# Sheet1.net
KiCad netlist of a schematic drawn in Altium Designer
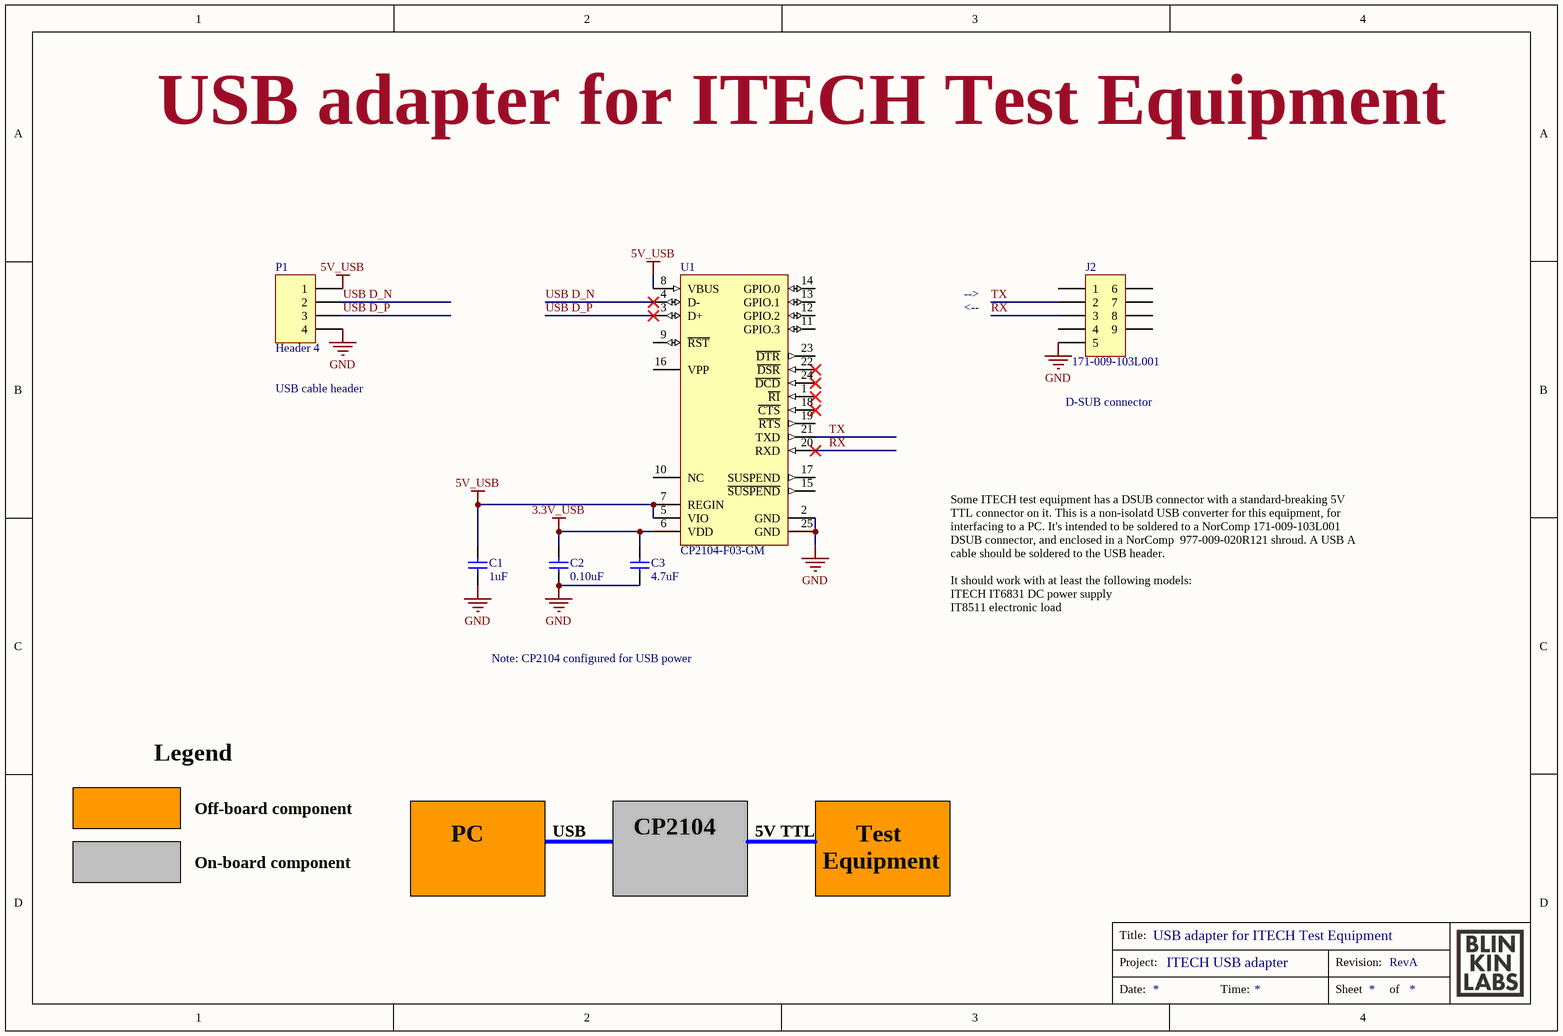
[diagram p0: Sheet1.SchDoc]

(export (version "E")
  (design (tool "Eeschema 10.0.6"))
  (components
    (comp (ref "C1")
      (value "1uF")
      (footprint "CAPC1005X06L")
      (description "CAP CER 1UF 10V X5R 0402")
      (fields
        (field (name "PARTNUMBER") "GRM155R61A105KE15D")
        (field (name "DIGI-KEY PART NUMBER") "490-3890-1-ND")
      )
      (libsource (lib "cap_murata") (part "CAPACITOR"))
    )
    (comp (ref "C2")
      (value "0.10uF")
      (footprint "CAPC1005X06L")
      (description "CAP CER 0.1UF 10V X5R 0402")
      (fields
        (field (name "DIGI-KEY PART NUMBER") "490-10009-1-ND")
        (field (name "MANUFACTURER") "Murata Electronics North America")
      )
      (libsource (lib "cap_murata") (part "CAPACITOR"))
    )
    (comp (ref "C3")
      (value "4.7uF")
      (footprint "CAPC1005X06L")
      (description "CAP CER 4.7UF 6.3V X5R 0402")
      (fields
        (field (name "PARTNUMBER") "GRM155R60J475ME47D")
        (field (name "DIGI-KEY PART NUMBER") "490-5915-1-ND")
      )
      (libsource (lib "cap_murata") (part "CAPACITOR"))
    )
    (comp (ref "J2")
      (value "171-009-103L001")
      (footprint "171-009-103L001")
      (description "CONN D-SUB PLUG 9POS PNL MNT, side mount DSUB connector")
      (fields (field (name "MANUFACTURER") "NorComp Inc.") (field (name "DIGIKEY PARTNUMBER") "209ME-ND"))
      (libsource (lib "Blinkinlabs") (part "171-009-103L001"))
    )
    (comp (ref "P1")
      (value "Header 4")
      (footprint "HDR1X4")
      (description "Header, 4-Pin")
      (fields (field (name "PUBLISHER") "Altium Limited"))
      (libsource (lib "Miscellaneous Connectors") (part "Header 4"))
    )
    (comp (ref "U1")
      (value "CP2104-F03-GM")
      (footprint "SLAB-QFN-24-2675x2675TP_M")
      (fields (field (name "MANUFACTURER") "Silicon Labs"))
      (libsource (lib "Altium Content Vault") (part "SLAB-CP2104-QFN-24-25"))
    )
  )
  (nets
    (net (code "1") (name "/RX") (class "Default")
      (node (ref "J2") (pin "3") (pinfunction "3_3") (pintype "passive"))
      (node (ref "U1") (pin "20") (pinfunction "RXD_20") (pintype "input"))
    )
    (net (code "2") (name "/TX") (class "Default")
      (node (ref "J2") (pin "2") (pinfunction "2_2") (pintype "passive"))
      (node (ref "U1") (pin "21") (pinfunction "TXD_21") (pintype "output"))
    )
    (net (code "3") (name "/USB D_N") (class "Default")
      (node (ref "P1") (pin "2") (pinfunction "2_2") (pintype "passive"))
      (node (ref "U1") (pin "4") (pinfunction "D-_4") (pintype "bidirectional"))
    )
    (net (code "4") (name "/USB D_P") (class "Default")
      (node (ref "P1") (pin "3") (pinfunction "3_3") (pintype "passive"))
      (node (ref "U1") (pin "3") (pinfunction "D+_3") (pintype "bidirectional"))
    )
    (net (code "5") (name "3.3V_USB") (class "Default")
      (node (ref "C2") (pin "2") (pinfunction "2_2") (pintype "passive"))
      (node (ref "C3") (pin "1") (pinfunction "1_1") (pintype "passive"))
      (node (ref "U1") (pin "6") (pinfunction "VDD_6") (pintype "power_in"))
    )
    (net (code "6") (name "5V_USB") (class "Default")
      (node (ref "C1") (pin "1") (pinfunction "1_1") (pintype "passive"))
      (node (ref "P1") (pin "1") (pinfunction "1_1") (pintype "passive"))
      (node (ref "U1") (pin "5") (pinfunction "VIO_5") (pintype "power_in"))
      (node (ref "U1") (pin "7") (pinfunction "REGIN_7") (pintype "power_in"))
      (node (ref "U1") (pin "8") (pinfunction "VBUS_8") (pintype "input"))
    )
    (net (code "7") (name "GND") (class "Default")
      (node (ref "C1") (pin "2") (pinfunction "2_2") (pintype "passive"))
      (node (ref "C2") (pin "1") (pinfunction "1_1") (pintype "passive"))
      (node (ref "C3") (pin "2") (pinfunction "2_2") (pintype "passive"))
      (node (ref "J2") (pin "5") (pinfunction "5_5") (pintype "passive"))
      (node (ref "P1") (pin "4") (pinfunction "4_4") (pintype "passive"))
      (node (ref "U1") (pin "2") (pinfunction "GND_2") (pintype "power_in"))
      (node (ref "U1") (pin "25") (pinfunction "GND_25") (pintype "power_in"))
    )
    (net (code "8") (name "unconnected-(J2-Pad1)") (class "Default")
      (node (ref "J2") (pin "1") (pinfunction "1_1") (pintype "passive"))
    )
    (net (code "9") (name "unconnected-(J2-Pad4)") (class "Default")
      (node (ref "J2") (pin "4") (pinfunction "4_4") (pintype "passive"))
    )
    (net (code "10") (name "unconnected-(J2-Pad6)") (class "Default")
      (node (ref "J2") (pin "6") (pinfunction "6_6") (pintype "passive"))
    )
    (net (code "11") (name "unconnected-(J2-Pad7)") (class "Default")
      (node (ref "J2") (pin "7") (pinfunction "7_7") (pintype "passive"))
    )
    (net (code "12") (name "unconnected-(J2-Pad8)") (class "Default")
      (node (ref "J2") (pin "8") (pinfunction "8_8") (pintype "passive"))
    )
    (net (code "13") (name "unconnected-(J2-Pad9)") (class "Default")
      (node (ref "J2") (pin "9") (pinfunction "9_9") (pintype "passive"))
    )
    (net (code "14") (name "unconnected-(U1-GPIO.0-Pad14)") (class "Default")
      (node (ref "U1") (pin "14") (pinfunction "GPIO.0_14") (pintype "bidirectional"))
    )
    (net (code "15") (name "unconnected-(U1-GPIO.1-Pad13)") (class "Default")
      (node (ref "U1") (pin "13") (pinfunction "GPIO.1_13") (pintype "bidirectional"))
    )
    (net (code "16") (name "unconnected-(U1-GPIO.2-Pad12)") (class "Default")
      (node (ref "U1") (pin "12") (pinfunction "GPIO.2_12") (pintype "bidirectional"))
    )
    (net (code "17") (name "unconnected-(U1-GPIO.3-Pad11)") (class "Default")
      (node (ref "U1") (pin "11") (pinfunction "GPIO.3_11") (pintype "bidirectional"))
    )
    (net (code "18") (name "unconnected-(U1-NC-Pad10)") (class "Default")
      (node (ref "U1") (pin "10") (pinfunction "NC_10") (pintype "passive"))
    )
    (net (code "19") (name "unconnected-(U1-SUSPEND-Pad17)") (class "Default")
      (node (ref "U1") (pin "17") (pinfunction "SUSPEND_17") (pintype "output"))
    )
    (net (code "20") (name "unconnected-(U1-VPP-Pad16)") (class "Default")
      (node (ref "U1") (pin "16") (pinfunction "VPP_16") (pintype "passive"))
    )
    (net (code "21") (name "unconnected-(U1-~{CTS}-Pad18)") (class "Default")
      (node (ref "U1") (pin "18") (pinfunction "~{CTS}_18") (pintype "input+no_connect"))
    )
    (net (code "22") (name "unconnected-(U1-~{DCD}-Pad24)") (class "Default")
      (node (ref "U1") (pin "24") (pinfunction "~{DCD}_24") (pintype "input+no_connect"))
    )
    (net (code "23") (name "unconnected-(U1-~{DSR}-Pad22)") (class "Default")
      (node (ref "U1") (pin "22") (pinfunction "~{DSR}_22") (pintype "input+no_connect"))
    )
    (net (code "24") (name "unconnected-(U1-~{DTR}-Pad23)") (class "Default")
      (node (ref "U1") (pin "23") (pinfunction "~{DTR}_23") (pintype "output"))
    )
    (net (code "25") (name "unconnected-(U1-~{RI}-Pad1)") (class "Default")
      (node (ref "U1") (pin "1") (pinfunction "~{RI}_1") (pintype "input+no_connect"))
    )
    (net (code "26") (name "unconnected-(U1-~{RST}-Pad9)") (class "Default")
      (node (ref "U1") (pin "9") (pinfunction "~{RST}_9") (pintype "bidirectional"))
    )
    (net (code "27") (name "unconnected-(U1-~{RTS}-Pad19)") (class "Default")
      (node (ref "U1") (pin "19") (pinfunction "~{RTS}_19") (pintype "output"))
    )
    (net (code "28") (name "unconnected-(U1-~{SUSPEND}-Pad15)") (class "Default")
      (node (ref "U1") (pin "15") (pinfunction "~{SUSPEND}_15") (pintype "output"))
    )
  )
)
